# TicTacToe.net
KiCad netlist of a schematic drawn in EAGLE
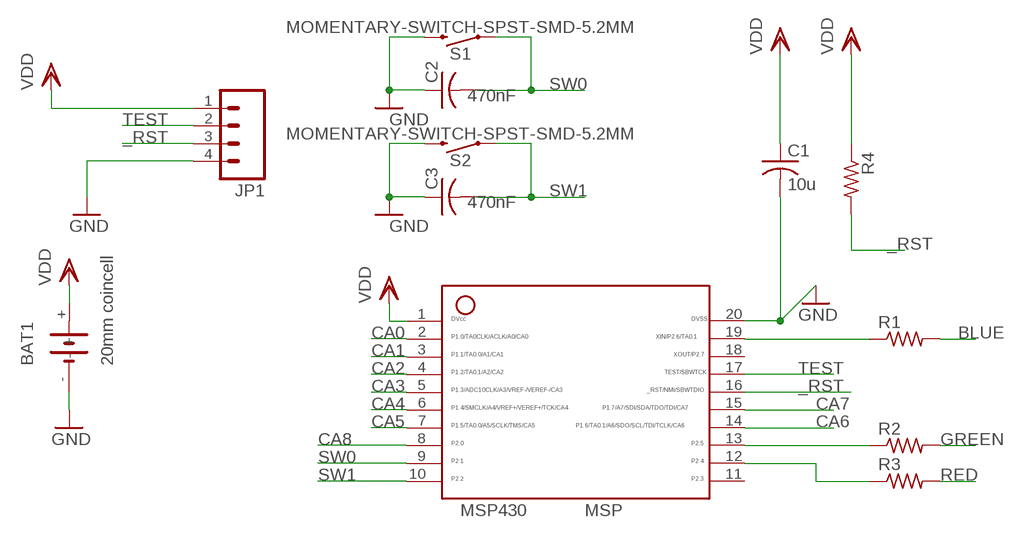
[diagram p0: schematic, sheet 1]
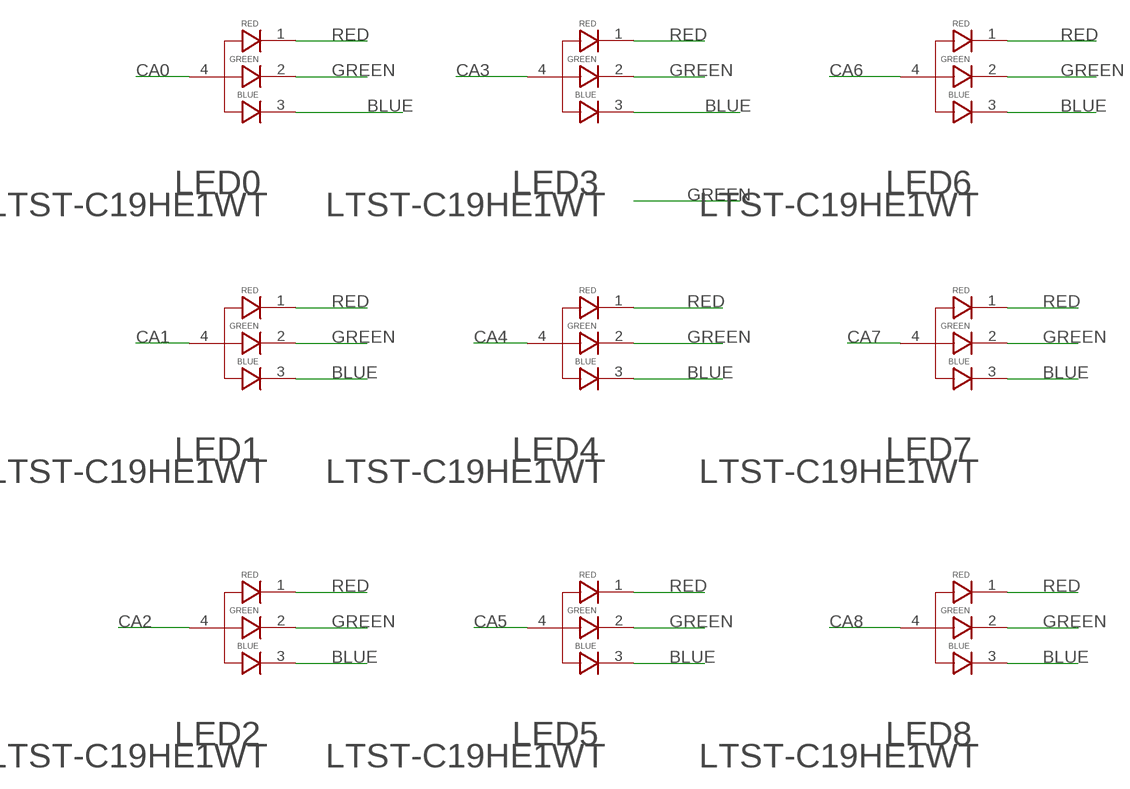
[diagram p1: schematic, sheet 2]

(export (version "E")
  (design (tool "Eeschema 10.0.6"))
  (components
    (comp (ref "LED0")
      (value "LTST-C19HE1WT")
      (footprint "eagle-import:LED_LTST-C19HE1WT")
      (fields (field (name "DIGI-KEY_PART_NUMBER") "160-2162-1-ND") (field (name "MF") "Lite-On Inc."))
      (libsource (lib "eagle-import") (part "LTST-C19HE1WT"))
    )
    (comp (ref "LED1")
      (value "LTST-C19HE1WT")
      (footprint "eagle-import:LED_LTST-C19HE1WT")
      (fields (field (name "DIGI-KEY_PART_NUMBER") "160-2162-1-ND") (field (name "MF") "Lite-On Inc."))
      (libsource (lib "eagle-import") (part "LTST-C19HE1WT"))
    )
    (comp (ref "LED2")
      (value "LTST-C19HE1WT")
      (footprint "eagle-import:LED_LTST-C19HE1WT")
      (fields (field (name "DIGI-KEY_PART_NUMBER") "160-2162-1-ND") (field (name "MF") "Lite-On Inc."))
      (libsource (lib "eagle-import") (part "LTST-C19HE1WT"))
    )
    (comp (ref "LED3")
      (value "LTST-C19HE1WT")
      (footprint "eagle-import:LED_LTST-C19HE1WT")
      (fields (field (name "DIGI-KEY_PART_NUMBER") "160-2162-1-ND") (field (name "MF") "Lite-On Inc."))
      (libsource (lib "eagle-import") (part "LTST-C19HE1WT"))
    )
    (comp (ref "LED4")
      (value "LTST-C19HE1WT")
      (footprint "eagle-import:LED_LTST-C19HE1WT")
      (fields (field (name "DIGI-KEY_PART_NUMBER") "160-2162-1-ND") (field (name "MF") "Lite-On Inc."))
      (libsource (lib "eagle-import") (part "LTST-C19HE1WT"))
    )
    (comp (ref "LED5")
      (value "LTST-C19HE1WT")
      (footprint "eagle-import:LED_LTST-C19HE1WT")
      (fields (field (name "DIGI-KEY_PART_NUMBER") "160-2162-1-ND") (field (name "MF") "Lite-On Inc."))
      (libsource (lib "eagle-import") (part "LTST-C19HE1WT"))
    )
    (comp (ref "LED6")
      (value "LTST-C19HE1WT")
      (footprint "eagle-import:LED_LTST-C19HE1WT")
      (fields (field (name "DIGI-KEY_PART_NUMBER") "160-2162-1-ND") (field (name "MF") "Lite-On Inc."))
      (libsource (lib "eagle-import") (part "LTST-C19HE1WT"))
    )
    (comp (ref "LED7")
      (value "LTST-C19HE1WT")
      (footprint "eagle-import:LED_LTST-C19HE1WT")
      (fields (field (name "DIGI-KEY_PART_NUMBER") "160-2162-1-ND") (field (name "MF") "Lite-On Inc."))
      (libsource (lib "eagle-import") (part "LTST-C19HE1WT"))
    )
    (comp (ref "LED8")
      (value "LTST-C19HE1WT")
      (footprint "eagle-import:LED_LTST-C19HE1WT")
      (fields (field (name "DIGI-KEY_PART_NUMBER") "160-2162-1-ND") (field (name "MF") "Lite-On Inc."))
      (libsource (lib "eagle-import") (part "LTST-C19HE1WT"))
    )
    (comp (ref "BAT1")
      (value "20mm coincell")
      (footprint "eagle-import:BAT_1060TR")
      (fields
        (field (name "DIGI-KEY_PART_NUMBER") "36-1060CT-ND")
        (field (name "MF") "Keystone")
        (field (name "MP") "1060TR")
      )
      (libsource (lib "eagle-import") (part "1060TR"))
    )
    (comp (ref "C1")
      (value "10u")
      (footprint "eagle-import:C1206")
      (libsource (lib "eagle-import") (part "C-USC1206"))
    )
    (comp (ref "C2")
      (value "470nF")
      (footprint "eagle-import:C0805")
      (libsource (lib "eagle-import") (part "C-USC0805"))
    )
    (comp (ref "C3")
      (value "470nF")
      (footprint "eagle-import:C0805")
      (libsource (lib "eagle-import") (part "C-USC0805"))
    )
    (comp (ref "JP1")
      (value "M04LOCK")
      (footprint "eagle-import:1X04_LOCK")
      (libsource (lib "eagle-import") (part "M04LOCK"))
    )
    (comp (ref "MSP430")
      (value "MSP")
      (footprint "eagle-import:20_PIN")
      (libsource (lib "eagle-import") (part "MSP430"))
    )
    (comp (ref "R1")
      (value "R-US_R0805")
      (footprint "eagle-import:R0805")
      (libsource (lib "eagle-import") (part "R-US_R0805"))
    )
    (comp (ref "R2")
      (value "R-US_R0805")
      (footprint "eagle-import:R0805")
      (libsource (lib "eagle-import") (part "R-US_R0805"))
    )
    (comp (ref "R3")
      (value "R-US_R0805")
      (footprint "eagle-import:R0805")
      (libsource (lib "eagle-import") (part "R-US_R0805"))
    )
    (comp (ref "R4")
      (value "R-US_R0805")
      (footprint "eagle-import:R0805")
      (libsource (lib "eagle-import") (part "R-US_R0805"))
    )
    (comp (ref "S1")
      (value "MOMENTARY-SWITCH-SPST-SMD-5.2MM")
      (footprint "eagle-import:TACTILE_SWITCH_SMD_5.2MM")
      (libsource (lib "eagle-import") (part "MOMENTARY-SWITCH-SPST-SMD-5.2MM"))
    )
    (comp (ref "S2")
      (value "MOMENTARY-SWITCH-SPST-SMD-5.2MM")
      (footprint "eagle-import:TACTILE_SWITCH_SMD_5.2MM")
      (libsource (lib "eagle-import") (part "MOMENTARY-SWITCH-SPST-SMD-5.2MM"))
    )
  )
  (nets
    (net (code "1") (name "BLUE") (class "Default")
      (node (ref "LED0") (pin "3") (pinfunction "3_3") (pintype "passive"))
      (node (ref "LED1") (pin "3") (pinfunction "3_3") (pintype "passive"))
      (node (ref "LED2") (pin "3") (pinfunction "3_3") (pintype "passive"))
      (node (ref "LED3") (pin "3") (pinfunction "3_3") (pintype "passive"))
      (node (ref "LED4") (pin "3") (pinfunction "3_3") (pintype "passive"))
      (node (ref "LED5") (pin "3") (pinfunction "3_3") (pintype "passive"))
      (node (ref "LED6") (pin "3") (pinfunction "3_3") (pintype "passive"))
      (node (ref "LED7") (pin "3") (pinfunction "3_3") (pintype "passive"))
      (node (ref "LED8") (pin "3") (pinfunction "3_3") (pintype "passive"))
      (node (ref "R1") (pin "2") (pinfunction "2_2") (pintype "passive"))
    )
    (net (code "2") (name "CA0") (class "Default")
      (node (ref "LED0") (pin "4") (pinfunction "4_4") (pintype "passive"))
      (node (ref "MSP430") (pin "2") (pinfunction "2_2") (pintype "bidirectional"))
    )
    (net (code "3") (name "CA1") (class "Default")
      (node (ref "LED1") (pin "4") (pinfunction "4_4") (pintype "passive"))
      (node (ref "MSP430") (pin "3") (pinfunction "3_3") (pintype "bidirectional"))
    )
    (net (code "4") (name "CA2") (class "Default")
      (node (ref "LED2") (pin "4") (pinfunction "4_4") (pintype "passive"))
      (node (ref "MSP430") (pin "4") (pinfunction "4_4") (pintype "bidirectional"))
    )
    (net (code "5") (name "CA3") (class "Default")
      (node (ref "LED3") (pin "4") (pinfunction "4_4") (pintype "passive"))
      (node (ref "MSP430") (pin "5") (pinfunction "5_5") (pintype "bidirectional"))
    )
    (net (code "6") (name "CA4") (class "Default")
      (node (ref "LED4") (pin "4") (pinfunction "4_4") (pintype "passive"))
      (node (ref "MSP430") (pin "6") (pinfunction "6_6") (pintype "bidirectional"))
    )
    (net (code "7") (name "CA5") (class "Default")
      (node (ref "LED5") (pin "4") (pinfunction "4_4") (pintype "passive"))
      (node (ref "MSP430") (pin "7") (pinfunction "7_7") (pintype "bidirectional"))
    )
    (net (code "8") (name "CA6") (class "Default")
      (node (ref "LED6") (pin "4") (pinfunction "4_4") (pintype "passive"))
      (node (ref "MSP430") (pin "14") (pinfunction "14_14") (pintype "bidirectional"))
    )
    (net (code "9") (name "CA7") (class "Default")
      (node (ref "LED7") (pin "4") (pinfunction "4_4") (pintype "passive"))
      (node (ref "MSP430") (pin "15") (pinfunction "15_15") (pintype "bidirectional"))
    )
    (net (code "10") (name "CA8") (class "Default")
      (node (ref "LED8") (pin "4") (pinfunction "4_4") (pintype "passive"))
      (node (ref "MSP430") (pin "8") (pinfunction "8_8") (pintype "bidirectional"))
    )
    (net (code "11") (name "GND") (class "Default")
      (node (ref "BAT1") (pin "-") (pinfunction "-_-") (pintype "power_in"))
      (node (ref "C1") (pin "2") (pinfunction "2_2") (pintype "passive"))
      (node (ref "C2") (pin "1") (pinfunction "1_1") (pintype "passive"))
      (node (ref "C3") (pin "1") (pinfunction "1_1") (pintype "passive"))
      (node (ref "JP1") (pin "4") (pinfunction "4_4") (pintype "passive"))
      (node (ref "MSP430") (pin "20") (pinfunction "20_20") (pintype "bidirectional"))
      (node (ref "S1") (pin "3") (pinfunction "2_3") (pintype "passive"))
      (node (ref "S2") (pin "3") (pinfunction "2_3") (pintype "passive"))
    )
    (net (code "12") (name "GREEN") (class "Default")
      (node (ref "LED0") (pin "2") (pinfunction "2_2") (pintype "passive"))
      (node (ref "LED1") (pin "2") (pinfunction "2_2") (pintype "passive"))
      (node (ref "LED2") (pin "2") (pinfunction "2_2") (pintype "passive"))
      (node (ref "LED3") (pin "2") (pinfunction "2_2") (pintype "passive"))
      (node (ref "LED4") (pin "2") (pinfunction "2_2") (pintype "passive"))
      (node (ref "LED5") (pin "2") (pinfunction "2_2") (pintype "passive"))
      (node (ref "LED6") (pin "2") (pinfunction "2_2") (pintype "passive"))
      (node (ref "LED7") (pin "2") (pinfunction "2_2") (pintype "passive"))
      (node (ref "LED8") (pin "2") (pinfunction "2_2") (pintype "passive"))
      (node (ref "R2") (pin "2") (pinfunction "2_2") (pintype "passive"))
    )
    (net (code "13") (name "Net-(MSP430-Pad12)") (class "Default")
      (node (ref "MSP430") (pin "12") (pinfunction "12_12") (pintype "bidirectional"))
      (node (ref "R3") (pin "1") (pinfunction "1_1") (pintype "passive"))
    )
    (net (code "14") (name "Net-(MSP430-Pad13)") (class "Default")
      (node (ref "MSP430") (pin "13") (pinfunction "13_13") (pintype "bidirectional"))
      (node (ref "R2") (pin "1") (pinfunction "1_1") (pintype "passive"))
    )
    (net (code "15") (name "Net-(MSP430-Pad19)") (class "Default")
      (node (ref "MSP430") (pin "19") (pinfunction "19_19") (pintype "bidirectional"))
      (node (ref "R1") (pin "1") (pinfunction "1_1") (pintype "passive"))
    )
    (net (code "16") (name "RED") (class "Default")
      (node (ref "LED0") (pin "1") (pinfunction "1_1") (pintype "passive"))
      (node (ref "LED1") (pin "1") (pinfunction "1_1") (pintype "passive"))
      (node (ref "LED2") (pin "1") (pinfunction "1_1") (pintype "passive"))
      (node (ref "LED3") (pin "1") (pinfunction "1_1") (pintype "passive"))
      (node (ref "LED4") (pin "1") (pinfunction "1_1") (pintype "passive"))
      (node (ref "LED5") (pin "1") (pinfunction "1_1") (pintype "passive"))
      (node (ref "LED6") (pin "1") (pinfunction "1_1") (pintype "passive"))
      (node (ref "LED7") (pin "1") (pinfunction "1_1") (pintype "passive"))
      (node (ref "LED8") (pin "1") (pinfunction "1_1") (pintype "passive"))
      (node (ref "R3") (pin "2") (pinfunction "2_2") (pintype "passive"))
    )
    (net (code "17") (name "SW0") (class "Default")
      (node (ref "C2") (pin "2") (pinfunction "2_2") (pintype "passive"))
      (node (ref "MSP430") (pin "9") (pinfunction "9_9") (pintype "bidirectional"))
      (node (ref "S1") (pin "1") (pinfunction "1_1") (pintype "passive"))
    )
    (net (code "18") (name "SW1") (class "Default")
      (node (ref "C3") (pin "2") (pinfunction "2_2") (pintype "passive"))
      (node (ref "MSP430") (pin "10") (pinfunction "10_10") (pintype "bidirectional"))
      (node (ref "S2") (pin "1") (pinfunction "1_1") (pintype "passive"))
    )
    (net (code "19") (name "TEST") (class "Default")
      (node (ref "JP1") (pin "2") (pinfunction "2_2") (pintype "passive"))
      (node (ref "MSP430") (pin "17") (pinfunction "17_17") (pintype "bidirectional"))
    )
    (net (code "20") (name "VDD") (class "Default")
      (node (ref "BAT1") (pin "+") (pinfunction "+_+") (pintype "power_in"))
      (node (ref "C1") (pin "1") (pinfunction "1_1") (pintype "passive"))
      (node (ref "JP1") (pin "1") (pinfunction "1_1") (pintype "passive"))
      (node (ref "MSP430") (pin "1") (pinfunction "1_1") (pintype "bidirectional"))
      (node (ref "R4") (pin "1") (pinfunction "1_1") (pintype "passive"))
    )
    (net (code "21") (name "_RST") (class "Default")
      (node (ref "JP1") (pin "3") (pinfunction "3_3") (pintype "passive"))
      (node (ref "MSP430") (pin "16") (pinfunction "16_16") (pintype "bidirectional"))
      (node (ref "R4") (pin "2") (pinfunction "2_2") (pintype "passive"))
    )
    (net (code "22") (name "unconnected-(MSP430-Pad11)") (class "Default")
      (node (ref "MSP430") (pin "11") (pinfunction "11_11") (pintype "bidirectional"))
    )
    (net (code "23") (name "unconnected-(MSP430-Pad18)") (class "Default")
      (node (ref "MSP430") (pin "18") (pinfunction "18_18") (pintype "bidirectional"))
    )
  )
)
